# WIRELESS.net
KiCad netlist of a schematic drawn in Altium Designer
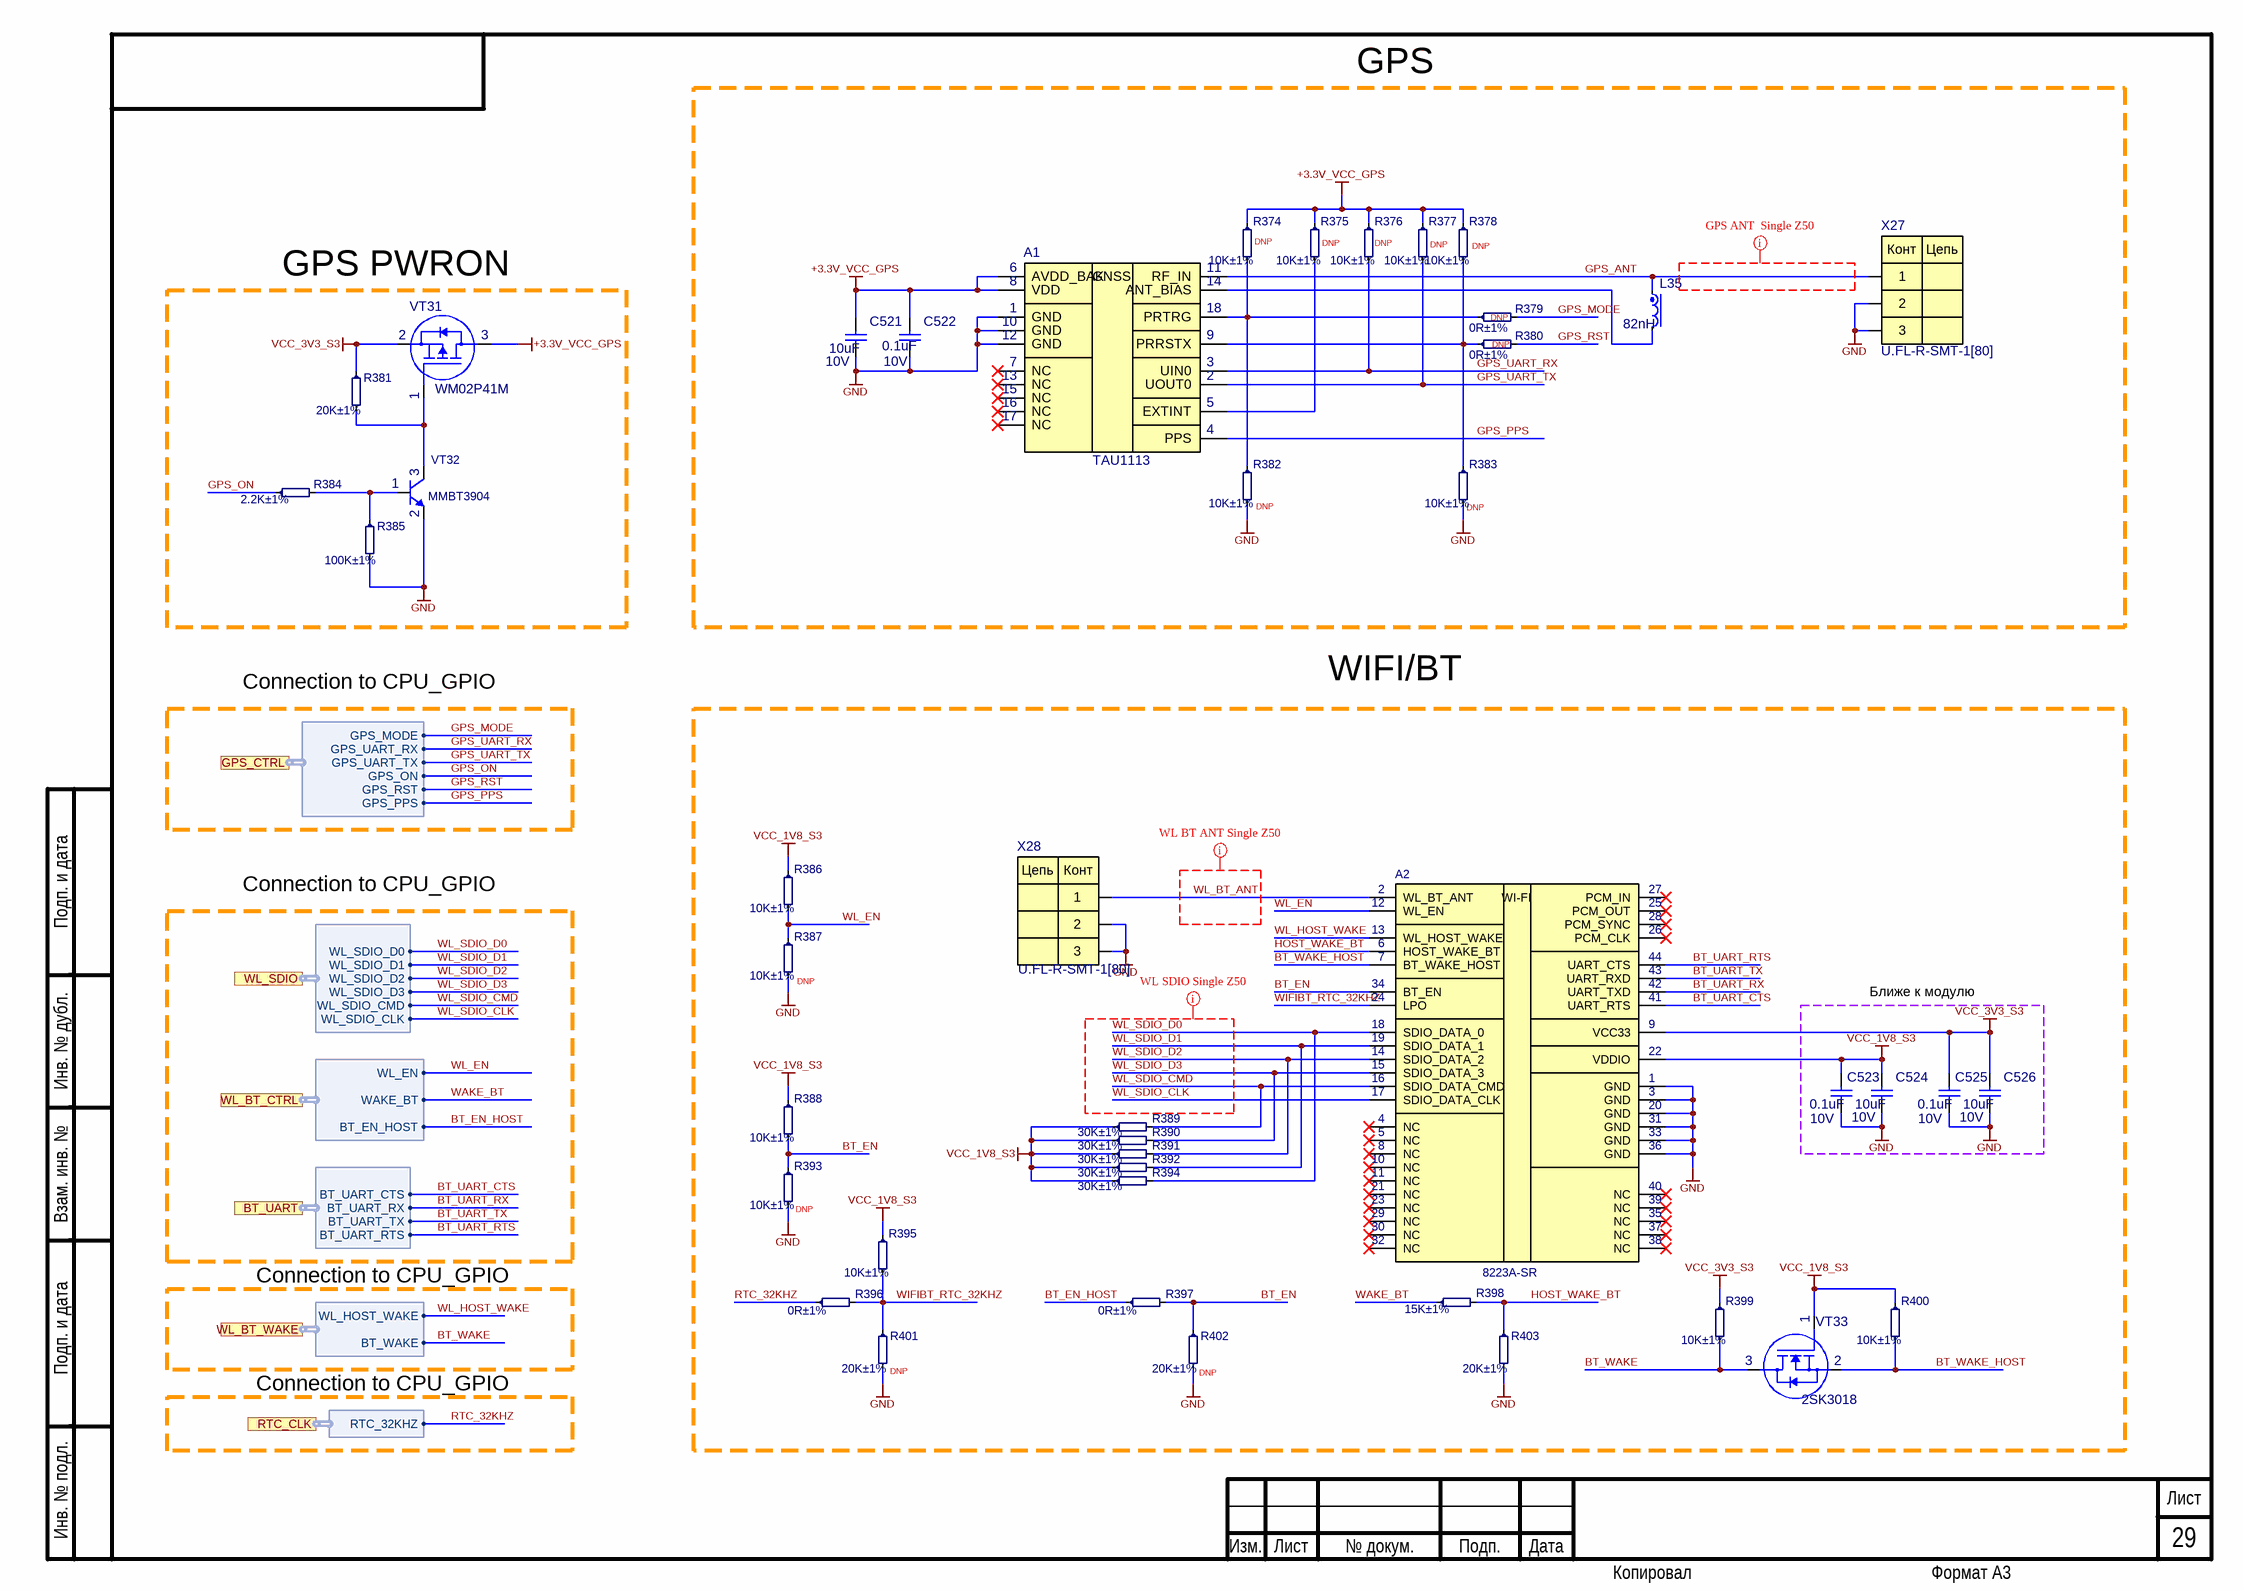
[diagram p0: WIRELESS.SchDoc]

(export (version "E")
  (design (tool "Eeschema 10.0.6"))
  (components
    (comp (ref "A1")
      (value "TAU1113")
      (footprint "TAU1103")
      (description "GNSS Positioning Module")
      (fields (field (name "MANUFACTURER") "Allystar"))
      (libsource (lib "ATB") (part "TAU1103"))
    )
    (comp (ref "A2")
      (value "8223A-SR")
      (footprint "FG6233ASRB-01")
      (description "WIFI/BT")
      (fields (field (name "MANUFACTURER") "FN-LINK"))
      (libsource (lib "LIB_RK") (part "FG6233ASRB-01"))
    )
    (comp (ref "C521")
      (value "10uF")
      (footprint "C0402")
      (fields
        (field (name "PART NUMBER") "0402-X5R-10V-10uF±20")
        (field (name "VOLTAGE") "10V")
        (field (name "TOLERANCE") "20%")
        (field (name "MANUFACTURER") "Samsung")
      )
      (libsource (lib "ATB") (part "C"))
    )
    (comp (ref "C522")
      (value "0.1uF")
      (footprint "C0402")
      (fields
        (field (name "PART NUMBER") "0402-X5R-10V-0.1uF±10%")
        (field (name "VOLTAGE") "10V")
        (field (name "TOLERANCE") "10%")
        (field (name "MANUFACTURER") "Yageo")
      )
      (libsource (lib "ATB") (part "C"))
    )
    (comp (ref "C523")
      (value "0.1uF")
      (footprint "C0402")
      (fields
        (field (name "PART NUMBER") "0402-X5R-10V-0.1uF±10%")
        (field (name "VOLTAGE") "10V")
        (field (name "TOLERANCE") "10%")
        (field (name "MANUFACTURER") "Yageo")
      )
      (libsource (lib "ATB") (part "C"))
    )
    (comp (ref "C524")
      (value "10uF")
      (footprint "C0402")
      (fields
        (field (name "PART NUMBER") "0402-X5R-10V-10uF±20%")
        (field (name "VOLTAGE") "10V")
        (field (name "TOLERANCE") "20%")
        (field (name "MANUFACTURER") "Murata Electronics")
      )
      (libsource (lib "ATB") (part "C"))
    )
    (comp (ref "C525")
      (value "0.1uF")
      (footprint "C0402")
      (fields
        (field (name "PART NUMBER") "0402-X5R-10V-0.1uF±10%")
        (field (name "VOLTAGE") "10V")
        (field (name "TOLERANCE") "10%")
        (field (name "MANUFACTURER") "Yageo")
      )
      (libsource (lib "ATB") (part "C"))
    )
    (comp (ref "C526")
      (value "10uF")
      (footprint "C0402")
      (fields
        (field (name "PART NUMBER") "0402-X5R-10V-10uF±20%")
        (field (name "VOLTAGE") "10V")
        (field (name "TOLERANCE") "20%")
        (field (name "MANUFACTURER") "Murata Electronics")
      )
      (libsource (lib "ATB") (part "C"))
    )
    (comp (ref "L35")
      (value "82nH")
      (footprint "L0402")
      (fields
        (field (name "PART NUMBER") "0402-150mA-82nH±5%")
        (field (name "TOLERANCE") "5%")
        (field (name "MANUFACTURER") "Murata Electronics")
      )
      (libsource (lib "ATB") (part "L"))
    )
    (comp (ref "R374")
      (value "10K±1%")
      (footprint "R0402")
      (description "Chip Resistor 0402 10kΩ ±1% 50V ±100ppm/℃ Thick Film")
      (fields (field (name "PART NUMBER") "0402-0.0625W-10K-100ppm±1%") (field (name "TOLERANCE") "1%"))
      (libsource (lib "ATB") (part "R"))
    )
    (comp (ref "R375")
      (value "10K±1%")
      (footprint "R0402")
      (description "Chip Resistor 0402 10kΩ ±1% 50V ±100ppm/℃ Thick Film")
      (fields (field (name "PART NUMBER") "0402-0.0625W-10K-100ppm±1%") (field (name "TOLERANCE") "1%"))
      (libsource (lib "ATB") (part "R"))
    )
    (comp (ref "R376")
      (value "10K±1%")
      (footprint "R0402")
      (description "Chip Resistor 0402 10kΩ ±1% 50V ±100ppm/℃ Thick Film")
      (fields (field (name "PART NUMBER") "0402-0.0625W-10K-100ppm±1%") (field (name "TOLERANCE") "1%"))
      (libsource (lib "ATB") (part "R"))
    )
    (comp (ref "R377")
      (value "10K±1%")
      (footprint "R0402")
      (description "Chip Resistor 0402 10kΩ ±1% 50V ±100ppm/℃ Thick Film")
      (fields (field (name "PART NUMBER") "0402-0.0625W-10K-100ppm±1%") (field (name "TOLERANCE") "1%"))
      (libsource (lib "ATB") (part "R"))
    )
    (comp (ref "R378")
      (value "10K±1%")
      (footprint "R0402")
      (description "Chip Resistor 0402 10kΩ ±1% 50V ±100ppm/℃ Thick Film")
      (fields (field (name "PART NUMBER") "0402-0.0625W-10K-100ppm±1%") (field (name "TOLERANCE") "1%"))
      (libsource (lib "ATB") (part "R"))
    )
    (comp (ref "R379")
      (value "0R±1%")
      (footprint "R0402")
      (description "Chip Resistor 0402 0Ω ±1% 50V ±100ppm/℃ Thick Film")
      (fields (field (name "PART NUMBER") "0402-0.0625W-0R-100ppm±1%") (field (name "TOLERANCE") "1%"))
      (libsource (lib "ATB") (part "R"))
    )
    (comp (ref "R380")
      (value "0R±1%")
      (footprint "R0402")
      (description "Chip Resistor 0402 0Ω ±1% 50V ±100ppm/℃ Thick Film")
      (fields (field (name "PART NUMBER") "0402-0.0625W-0R-100ppm±1%") (field (name "TOLERANCE") "1%"))
      (libsource (lib "ATB") (part "R"))
    )
    (comp (ref "R381")
      (value "20K±1%")
      (footprint "R0402")
      (description "Chip Resistor 0402 20kΩ ±1% 50V ±100ppm/℃ Thick Film")
      (fields (field (name "PART NUMBER") "0402-0.0625W-20K-100ppm±1%") (field (name "TOLERANCE") "1%"))
      (libsource (lib "ATB") (part "R"))
    )
    (comp (ref "R382")
      (value "10K±1%")
      (footprint "R0402")
      (description "Chip Resistor 0402 10kΩ ±1% 50V ±100ppm/℃ Thick Film")
      (fields (field (name "PART NUMBER") "0402-0.0625W-10K-100ppm±1%") (field (name "TOLERANCE") "1%"))
      (libsource (lib "ATB") (part "R"))
    )
    (comp (ref "R383")
      (value "10K±1%")
      (footprint "R0402")
      (description "Chip Resistor 0402 10kΩ ±1% 50V ±100ppm/℃ Thick Film")
      (fields (field (name "PART NUMBER") "0402-0.0625W-10K-100ppm±1%") (field (name "TOLERANCE") "1%"))
      (libsource (lib "ATB") (part "R"))
    )
    (comp (ref "R384")
      (value "2.2K±1%")
      (footprint "R0402")
      (fields
        (field (name "PART NUMBER") "0402-0.0625W-2.2K-100ppm±1%")
        (field (name "TOLERANCE") "1%")
        (field (name "MANUFACTURER") "Yageo")
      )
      (libsource (lib "ATB") (part "R"))
    )
    (comp (ref "R385")
      (value "100K±1%")
      (footprint "R0402")
      (description "Chip Resistor 0402 100kΩ ±1% 50V ±100ppm/℃ Thick Film")
      (fields (field (name "PART NUMBER") "0402-0.0625W-100K-100ppm±1%") (field (name "TOLERANCE") "1%"))
      (libsource (lib "ATB") (part "R"))
    )
    (comp (ref "R386")
      (value "10K±1%")
      (footprint "R0402")
      (description "Chip Resistor 0402 10kΩ ±1% 50V ±100ppm/℃ Thick Film")
      (fields (field (name "PART NUMBER") "0402-0.0625W-10K-100ppm±1%") (field (name "TOLERANCE") "1%"))
      (libsource (lib "ATB") (part "R"))
    )
    (comp (ref "R387")
      (value "10K±1%")
      (footprint "R0402")
      (description "Chip Resistor 0402 10kΩ ±1% 50V ±100ppm/℃ Thick Film")
      (fields (field (name "PART NUMBER") "0402-0.0625W-10K-100ppm±1%") (field (name "TOLERANCE") "1%"))
      (libsource (lib "ATB") (part "R"))
    )
    (comp (ref "R388")
      (value "10K±1%")
      (footprint "R0402")
      (description "Chip Resistor 0402 10kΩ ±1% 50V ±100ppm/℃ Thick Film")
      (fields (field (name "PART NUMBER") "0402-0.0625W-10K-100ppm±1%") (field (name "TOLERANCE") "1%"))
      (libsource (lib "ATB") (part "R"))
    )
    (comp (ref "R389")
      (value "30K±1%")
      (footprint "R0402")
      (fields
        (field (name "PART NUMBER") "0402-0.0625W-30K-100ppm±1%")
        (field (name "TOLERANCE") "1%")
        (field (name "MANUFACTURER") "Yageo")
      )
      (libsource (lib "ATB") (part "R"))
    )
    (comp (ref "R390")
      (value "30K±1%")
      (footprint "R0402")
      (fields
        (field (name "PART NUMBER") "0402-0.0625W-30K-100ppm±1%")
        (field (name "TOLERANCE") "1%")
        (field (name "MANUFACTURER") "Yageo")
      )
      (libsource (lib "ATB") (part "R"))
    )
    (comp (ref "R391")
      (value "30K±1%")
      (footprint "R0402")
      (fields
        (field (name "PART NUMBER") "0402-0.0625W-30K-100ppm±1%")
        (field (name "TOLERANCE") "1%")
        (field (name "MANUFACTURER") "Yageo")
      )
      (libsource (lib "ATB") (part "R"))
    )
    (comp (ref "R392")
      (value "30K±1%")
      (footprint "R0402")
      (fields
        (field (name "PART NUMBER") "0402-0.0625W-30K-100ppm±1%")
        (field (name "TOLERANCE") "1%")
        (field (name "MANUFACTURER") "Yageo")
      )
      (libsource (lib "ATB") (part "R"))
    )
    (comp (ref "R393")
      (value "10K±1%")
      (footprint "R0402")
      (description "Chip Resistor 0402 10kΩ ±1% 50V ±100ppm/℃ Thick Film")
      (fields (field (name "PART NUMBER") "0402-0.0625W-10K-100ppm±1%") (field (name "TOLERANCE") "1%"))
      (libsource (lib "ATB") (part "R"))
    )
    (comp (ref "R394")
      (value "30K±1%")
      (footprint "R0402")
      (fields
        (field (name "PART NUMBER") "0402-0.0625W-30K-100ppm±1%")
        (field (name "TOLERANCE") "1%")
        (field (name "MANUFACTURER") "Yageo")
      )
      (libsource (lib "ATB") (part "R"))
    )
    (comp (ref "R395")
      (value "10K±1%")
      (footprint "R0402")
      (description "Chip Resistor 0402 10kΩ ±1% 50V ±100ppm/℃ Thick Film")
      (fields (field (name "PART NUMBER") "0402-0.0625W-10K-100ppm±1%") (field (name "TOLERANCE") "1%"))
      (libsource (lib "ATB") (part "R"))
    )
    (comp (ref "R396")
      (value "0R±1%")
      (footprint "R0402")
      (description "Chip Resistor 0402 0Ω ±1% 50V ±100ppm/℃ Thick Film")
      (fields (field (name "PART NUMBER") "0402-0.0625W-0R-100ppm±1%") (field (name "TOLERANCE") "1%"))
      (libsource (lib "ATB") (part "R"))
    )
    (comp (ref "R397")
      (value "0R±1%")
      (footprint "R0402")
      (description "Chip Resistor 0402 0Ω ±1% 50V ±100ppm/℃ Thick Film")
      (fields (field (name "PART NUMBER") "0402-0.0625W-0R-100ppm±1%") (field (name "TOLERANCE") "1%"))
      (libsource (lib "ATB") (part "R"))
    )
    (comp (ref "R398")
      (value "15K±1%")
      (footprint "R0402")
      (fields
        (field (name "PART NUMBER") "0402-0.0625W-15K-100ppm±1%")
        (field (name "TOLERANCE") "1%")
        (field (name "MANUFACTURER") "Viking Tech Corp.(VIKING)")
      )
      (libsource (lib "ATB") (part "R"))
    )
    (comp (ref "R399")
      (value "10K±1%")
      (footprint "R0402")
      (description "Chip Resistor 0402 10kΩ ±1% 50V ±100ppm/℃ Thick Film")
      (fields (field (name "PART NUMBER") "0402-0.0625W-10K-100ppm±1%") (field (name "TOLERANCE") "1%"))
      (libsource (lib "ATB") (part "R"))
    )
    (comp (ref "R400")
      (value "10K±1%")
      (footprint "R0402")
      (description "Chip Resistor 0402 10kΩ ±1% 50V ±100ppm/℃ Thick Film")
      (fields (field (name "PART NUMBER") "0402-0.0625W-10K-100ppm±1%") (field (name "TOLERANCE") "1%"))
      (libsource (lib "ATB") (part "R"))
    )
    (comp (ref "R401")
      (value "20K±1%")
      (footprint "R0402")
      (description "Chip Resistor 0402 20kΩ ±1% 50V ±100ppm/℃ Thick Film")
      (fields (field (name "PART NUMBER") "0402-0.0625W-20K-100ppm±1%") (field (name "TOLERANCE") "1%"))
      (libsource (lib "ATB") (part "R"))
    )
    (comp (ref "R402")
      (value "20K±1%")
      (footprint "R0402")
      (description "Chip Resistor 0402 20kΩ ±1% 50V ±100ppm/℃ Thick Film")
      (fields (field (name "PART NUMBER") "0402-0.0625W-20K-100ppm±1%") (field (name "TOLERANCE") "1%"))
      (libsource (lib "ATB") (part "R"))
    )
    (comp (ref "R403")
      (value "20K±1%")
      (footprint "R0402")
      (description "Chip Resistor 0402 20kΩ ±1% 50V ±100ppm/℃ Thick Film")
      (fields (field (name "PART NUMBER") "0402-0.0625W-20K-100ppm±1%") (field (name "TOLERANCE") "1%"))
      (libsource (lib "ATB") (part "R"))
    )
    (comp (ref "VT31")
      (value "WM02P41M")
      (footprint "SOT23")
      (description "Small signal mosfet")
      (fields (field (name "VOLTAGE") "-20V") (field (name "MANUFACTURER") "Wayon"))
      (libsource (lib "ATB") (part "WM02P41M"))
    )
    (comp (ref "VT32")
      (value "MMBT3904")
      (footprint "SOT23")
      (description "NPN transistor")
      (fields (field (name "VOLTAGE") "40V") (field (name "MANUFACTURER") "Diotec Semiconductor"))
      (libsource (lib "ATB") (part "BC846BLT1G"))
    )
    (comp (ref "VT33")
      (value "2SK3018")
      (footprint "2SK3018")
      (description "N-Channel")
      (fields (field (name "MANUFACTURER") "KUU"))
      (libsource (lib "LIB_RK") (part "2SK3018"))
    )
    (comp (ref "X27")
      (value "U.FL-R-SMT-1[80]")
      (footprint "1909763-1")
      (description "U.FL-R-SMT-1")
      (fields (field (name "MANUFACTURER") "TE Connectivity"))
      (libsource (lib "ATB") (part "H3"))
    )
    (comp (ref "X28")
      (value "U.FL-R-SMT-1[80]")
      (footprint "1909763-1")
      (description "U.FL-R-SMT-1")
      (fields (field (name "MANUFACTURER") "TE Connectivity"))
      (libsource (lib "") (part "H3_1"))
    )
  )
  (nets
    (net (code "7") (name "+3.3V_VCC_GPS") (class "Default")
      (node (ref "A1") (pin "6") (pinfunction "AVDD_BAK_6") (pintype "passive"))
      (node (ref "A1") (pin "8") (pinfunction "VDD_8") (pintype "passive"))
      (node (ref "C521") (pin "2") (pinfunction "2_2") (pintype "passive"))
      (node (ref "C522") (pin "2") (pinfunction "2_2") (pintype "passive"))
      (node (ref "R374") (pin "1") (pinfunction "1_1") (pintype "passive"))
      (node (ref "R375") (pin "1") (pinfunction "1_1") (pintype "passive"))
      (node (ref "R376") (pin "1") (pinfunction "1_1") (pintype "passive"))
      (node (ref "R377") (pin "1") (pinfunction "1_1") (pintype "passive"))
      (node (ref "R378") (pin "1") (pinfunction "1_1") (pintype "passive"))
      (node (ref "VT31") (pin "3") (pinfunction "3_3") (pintype "passive"))
    )
    (net (code "8") (name "/BT_EN") (class "Default")
      (node (ref "A2") (pin "34") (pinfunction "BT_EN_34") (pintype "passive"))
      (node (ref "R388") (pin "2") (pinfunction "2_2") (pintype "passive"))
      (node (ref "R393") (pin "1") (pinfunction "1_1") (pintype "passive"))
      (node (ref "R397") (pin "2") (pinfunction "2_2") (pintype "passive"))
      (node (ref "R402") (pin "1") (pinfunction "1_1") (pintype "passive"))
    )
    (net (code "9") (name "/BT_EN_HOST") (class "Default")
      (node (ref "R397") (pin "1") (pinfunction "1_1") (pintype "passive"))
    )
    (net (code "10") (name "/BT_UART_CTS") (class "Default")
      (node (ref "A2") (pin "41") (pinfunction "UART_RTS_41") (pintype "passive"))
    )
    (net (code "11") (name "/BT_UART_RTS") (class "Default")
      (node (ref "A2") (pin "44") (pinfunction "UART_CTS_44") (pintype "passive"))
    )
    (net (code "12") (name "/BT_UART_RX") (class "Default")
      (node (ref "A2") (pin "42") (pinfunction "UART_TXD_42") (pintype "passive"))
    )
    (net (code "13") (name "/BT_UART_TX") (class "Default")
      (node (ref "A2") (pin "43") (pinfunction "UART_RXD_43") (pintype "passive"))
    )
    (net (code "14") (name "/BT_WAKE") (class "Default")
      (node (ref "R399") (pin "2") (pinfunction "2_2") (pintype "passive"))
      (node (ref "VT33") (pin "3") (pinfunction "D_3") (pintype "passive"))
    )
    (net (code "15") (name "/BT_WAKE_HOST") (class "Default")
      (node (ref "A2") (pin "7") (pinfunction "BT_WAKE_HOST_7") (pintype "passive"))
      (node (ref "R400") (pin "2") (pinfunction "2_2") (pintype "passive"))
      (node (ref "VT33") (pin "2") (pinfunction "S_2") (pintype "passive"))
    )
    (net (code "16") (name "/GPS_ANT") (class "Default")
      (node (ref "A1") (pin "11") (pinfunction "RF_IN_11") (pintype "passive"))
      (node (ref "L35") (pin "1") (pinfunction "1_1") (pintype "passive"))
      (node (ref "X27") (pin "1") (pinfunction "1_1") (pintype "passive"))
    )
    (net (code "17") (name "/GPS_MODE") (class "Default")
      (node (ref "R379") (pin "2") (pinfunction "2_2") (pintype "passive"))
    )
    (net (code "18") (name "/GPS_ON") (class "Default")
      (node (ref "R384") (pin "1") (pinfunction "1_1") (pintype "passive"))
    )
    (net (code "19") (name "/GPS_PPS") (class "Default")
      (node (ref "A1") (pin "4") (pinfunction "PPS_4") (pintype "passive"))
    )
    (net (code "20") (name "/GPS_RST") (class "Default")
      (node (ref "R380") (pin "2") (pinfunction "2_2") (pintype "passive"))
    )
    (net (code "21") (name "/GPS_UART_RX") (class "Default")
      (node (ref "A1") (pin "3") (pinfunction "UIN0_3") (pintype "passive"))
      (node (ref "R376") (pin "2") (pinfunction "2_2") (pintype "passive"))
    )
    (net (code "22") (name "/GPS_UART_TX") (class "Default")
      (node (ref "A1") (pin "2") (pinfunction "UOUT0_2") (pintype "passive"))
      (node (ref "R377") (pin "2") (pinfunction "2_2") (pintype "passive"))
    )
    (net (code "23") (name "/HOST_WAKE_BT") (class "Default")
      (node (ref "A2") (pin "6") (pinfunction "HOST_WAKE_BT_6") (pintype "passive"))
      (node (ref "R398") (pin "2") (pinfunction "2_2") (pintype "passive"))
      (node (ref "R403") (pin "1") (pinfunction "1_1") (pintype "passive"))
    )
    (net (code "24") (name "/RTC_32KHZ") (class "Default")
      (node (ref "R396") (pin "1") (pinfunction "1_1") (pintype "passive"))
    )
    (net (code "25") (name "/WAKE_BT") (class "Default")
      (node (ref "R398") (pin "1") (pinfunction "1_1") (pintype "passive"))
    )
    (net (code "26") (name "/WIFIBT_RTC_32KHZ") (class "Default")
      (node (ref "A2") (pin "24") (pinfunction "LPO_24") (pintype "passive"))
      (node (ref "R395") (pin "2") (pinfunction "2_2") (pintype "passive"))
      (node (ref "R396") (pin "2") (pinfunction "2_2") (pintype "passive"))
      (node (ref "R401") (pin "1") (pinfunction "1_1") (pintype "passive"))
    )
    (net (code "27") (name "/WL_BT_ANT") (class "Default")
      (node (ref "A2") (pin "2") (pinfunction "WL_BT_ANT_2") (pintype "passive"))
      (node (ref "X28") (pin "1") (pinfunction "1_1") (pintype "passive"))
    )
    (net (code "28") (name "/WL_EN") (class "Default")
      (node (ref "A2") (pin "12") (pinfunction "WL_EN_12") (pintype "passive"))
      (node (ref "R386") (pin "2") (pinfunction "2_2") (pintype "passive"))
      (node (ref "R387") (pin "1") (pinfunction "1_1") (pintype "passive"))
    )
    (net (code "29") (name "/WL_HOST_WAKE") (class "Default")
      (node (ref "A2") (pin "13") (pinfunction "WL_HOST_WAKE_13") (pintype "passive"))
    )
    (net (code "30") (name "/WL_SDIO_CLK") (class "Default")
      (node (ref "A2") (pin "17") (pinfunction "SDIO_DATA_CLK_17") (pintype "passive"))
    )
    (net (code "31") (name "/WL_SDIO_CMD") (class "Default")
      (node (ref "A2") (pin "16") (pinfunction "SDIO_DATA_CMD_16") (pintype "passive"))
      (node (ref "R389") (pin "2") (pinfunction "2_2") (pintype "passive"))
    )
    (net (code "32") (name "/WL_SDIO_D0") (class "Default")
      (node (ref "A2") (pin "18") (pinfunction "SDIO_DATA_0_18") (pintype "passive"))
      (node (ref "R394") (pin "2") (pinfunction "2_2") (pintype "passive"))
    )
    (net (code "33") (name "/WL_SDIO_D1") (class "Default")
      (node (ref "A2") (pin "19") (pinfunction "SDIO_DATA_1_19") (pintype "passive"))
      (node (ref "R392") (pin "2") (pinfunction "2_2") (pintype "passive"))
    )
    (net (code "34") (name "/WL_SDIO_D2") (class "Default")
      (node (ref "A2") (pin "14") (pinfunction "SDIO_DATA_2_14") (pintype "passive"))
      (node (ref "R391") (pin "2") (pinfunction "2_2") (pintype "passive"))
    )
    (net (code "35") (name "/WL_SDIO_D3") (class "Default")
      (node (ref "A2") (pin "15") (pinfunction "SDIO_DATA_3_15") (pintype "passive"))
      (node (ref "R390") (pin "2") (pinfunction "2_2") (pintype "passive"))
    )
    (net (code "42") (name "GND") (class "Default")
      (node (ref "A1") (pin "1") (pinfunction "GND_1") (pintype "passive"))
      (node (ref "A1") (pin "10") (pinfunction "GND_10") (pintype "passive"))
      (node (ref "A1") (pin "12") (pinfunction "GND_12") (pintype "passive"))
      (node (ref "A2") (pin "1") (pinfunction "GND_1") (pintype "passive"))
      (node (ref "A2") (pin "20") (pinfunction "GND_20") (pintype "passive"))
      (node (ref "A2") (pin "3") (pinfunction "GND_3") (pintype "passive"))
      (node (ref "A2") (pin "31") (pinfunction "GND_31") (pintype "passive"))
      (node (ref "A2") (pin "33") (pinfunction "GND_33") (pintype "passive"))
      (node (ref "A2") (pin "36") (pinfunction "GND_36") (pintype "passive"))
      (node (ref "C521") (pin "1") (pinfunction "1_1") (pintype "passive"))
      (node (ref "C522") (pin "1") (pinfunction "1_1") (pintype "passive"))
      (node (ref "C523") (pin "1") (pinfunction "1_1") (pintype "passive"))
      (node (ref "C524") (pin "1") (pinfunction "1_1") (pintype "passive"))
      (node (ref "C525") (pin "1") (pinfunction "1_1") (pintype "passive"))
      (node (ref "C526") (pin "1") (pinfunction "1_1") (pintype "passive"))
      (node (ref "R382") (pin "2") (pinfunction "2_2") (pintype "passive"))
      (node (ref "R383") (pin "2") (pinfunction "2_2") (pintype "passive"))
      (node (ref "R385") (pin "2") (pinfunction "2_2") (pintype "passive"))
      (node (ref "R387") (pin "2") (pinfunction "2_2") (pintype "passive"))
      (node (ref "R393") (pin "2") (pinfunction "2_2") (pintype "passive"))
      (node (ref "R401") (pin "2") (pinfunction "2_2") (pintype "passive"))
      (node (ref "R402") (pin "2") (pinfunction "2_2") (pintype "passive"))
      (node (ref "R403") (pin "2") (pinfunction "2_2") (pintype "passive"))
      (node (ref "VT32") (pin "2") (pinfunction "E_2") (pintype "passive"))
      (node (ref "X27") (pin "2") (pinfunction "2_2") (pintype "passive"))
      (node (ref "X27") (pin "3") (pinfunction "3_3") (pintype "passive"))
      (node (ref "X28") (pin "2") (pinfunction "2_2") (pintype "passive"))
      (node (ref "X28") (pin "3") (pinfunction "3_3") (pintype "passive"))
    )
    (net (code "43") (name "Net-(A1-ANT_BIAS)") (class "Default")
      (node (ref "A1") (pin "14") (pinfunction "ANT_BIAS_14") (pintype "passive"))
      (node (ref "L35") (pin "2") (pinfunction "2_2") (pintype "passive"))
    )
    (net (code "44") (name "Net-(A1-EXTINT)") (class "Default")
      (node (ref "A1") (pin "5") (pinfunction "EXTINT_5") (pintype "passive"))
      (node (ref "R375") (pin "2") (pinfunction "2_2") (pintype "passive"))
    )
    (net (code "45") (name "Net-(A1-PRRSTX)") (class "Default")
      (node (ref "A1") (pin "9") (pinfunction "PRRSTX_9") (pintype "passive"))
      (node (ref "R378") (pin "2") (pinfunction "2_2") (pintype "passive"))
      (node (ref "R380") (pin "1") (pinfunction "1_1") (pintype "passive"))
      (node (ref "R383") (pin "1") (pinfunction "1_1") (pintype "passive"))
    )
    (net (code "46") (name "Net-(A1-PRTRG)") (class "Default")
      (node (ref "A1") (pin "18") (pinfunction "PRTRG_18") (pintype "passive"))
      (node (ref "R374") (pin "2") (pinfunction "2_2") (pintype "passive"))
      (node (ref "R379") (pin "1") (pinfunction "1_1") (pintype "passive"))
      (node (ref "R382") (pin "1") (pinfunction "1_1") (pintype "passive"))
    )
    (net (code "47") (name "Net-(VT32-B)") (class "Default")
      (node (ref "R384") (pin "2") (pinfunction "2_2") (pintype "passive"))
      (node (ref "R385") (pin "1") (pinfunction "1_1") (pintype "passive"))
      (node (ref "VT32") (pin "1") (pinfunction "B_1") (pintype "passive"))
    )
    (net (code "48") (name "Net-(VT32-C)") (class "Default")
      (node (ref "R381") (pin "2") (pinfunction "2_2") (pintype "passive"))
      (node (ref "VT31") (pin "1") (pinfunction "1_1") (pintype "passive"))
      (node (ref "VT32") (pin "3") (pinfunction "C_3") (pintype "passive"))
    )
    (net (code "49") (name "VCC_1V8_S3") (class "Default")
      (node (ref "A2") (pin "22") (pinfunction "VDDIO_22") (pintype "passive"))
      (node (ref "C523") (pin "2") (pinfunction "2_2") (pintype "passive"))
      (node (ref "C524") (pin "2") (pinfunction "2_2") (pintype "passive"))
      (node (ref "R386") (pin "1") (pinfunction "1_1") (pintype "passive"))
      (node (ref "R388") (pin "1") (pinfunction "1_1") (pintype "passive"))
      (node (ref "R389") (pin "1") (pinfunction "1_1") (pintype "passive"))
      (node (ref "R390") (pin "1") (pinfunction "1_1") (pintype "passive"))
      (node (ref "R391") (pin "1") (pinfunction "1_1") (pintype "passive"))
      (node (ref "R392") (pin "1") (pinfunction "1_1") (pintype "passive"))
      (node (ref "R394") (pin "1") (pinfunction "1_1") (pintype "passive"))
      (node (ref "R395") (pin "1") (pinfunction "1_1") (pintype "passive"))
      (node (ref "R400") (pin "1") (pinfunction "1_1") (pintype "passive"))
      (node (ref "VT33") (pin "1") (pinfunction "G_1") (pintype "passive"))
    )
    (net (code "50") (name "VCC_3V3_S3") (class "Default")
      (node (ref "A2") (pin "9") (pinfunction "VCC33_9") (pintype "passive"))
      (node (ref "C525") (pin "2") (pinfunction "2_2") (pintype "passive"))
      (node (ref "C526") (pin "2") (pinfunction "2_2") (pintype "passive"))
      (node (ref "R381") (pin "1") (pinfunction "1_1") (pintype "passive"))
      (node (ref "R399") (pin "1") (pinfunction "1_1") (pintype "passive"))
      (node (ref "VT31") (pin "2") (pinfunction "2_2") (pintype "passive"))
    )
    (net (code "51") (name "unconnected-(A1-NC-Pad7)") (class "Default")
      (node (ref "A1") (pin "7") (pinfunction "NC_7") (pintype "passive+no_connect"))
    )
    (net (code "52") (name "unconnected-(A1-NC-Pad13)") (class "Default")
      (node (ref "A1") (pin "13") (pinfunction "NC_13") (pintype "passive+no_connect"))
    )
    (net (code "53") (name "unconnected-(A1-NC-Pad15)") (class "Default")
      (node (ref "A1") (pin "15") (pinfunction "NC_15") (pintype "passive+no_connect"))
    )
    (net (code "54") (name "unconnected-(A1-NC-Pad16)") (class "Default")
      (node (ref "A1") (pin "16") (pinfunction "NC_16") (pintype "passive+no_connect"))
    )
    (net (code "55") (name "unconnected-(A1-NC-Pad17)") (class "Default")
      (node (ref "A1") (pin "17") (pinfunction "NC_17") (pintype "passive+no_connect"))
    )
    (net (code "56") (name "unconnected-(A2-NC-Pad4)") (class "Default")
      (node (ref "A2") (pin "4") (pinfunction "NC_4") (pintype "passive+no_connect"))
    )
    (net (code "57") (name "unconnected-(A2-NC-Pad5)") (class "Default")
      (node (ref "A2") (pin "5") (pinfunction "NC_5") (pintype "passive+no_connect"))
    )
    (net (code "58") (name "unconnected-(A2-NC-Pad8)") (class "Default")
      (node (ref "A2") (pin "8") (pinfunction "NC_8") (pintype "passive+no_connect"))
    )
    (net (code "59") (name "unconnected-(A2-NC-Pad10)") (class "Default")
      (node (ref "A2") (pin "10") (pinfunction "NC_10") (pintype "passive+no_connect"))
    )
    (net (code "60") (name "unconnected-(A2-NC-Pad11)") (class "Default")
      (node (ref "A2") (pin "11") (pinfunction "NC_11") (pintype "passive+no_connect"))
    )
    (net (code "61") (name "unconnected-(A2-NC-Pad21)") (class "Default")
      (node (ref "A2") (pin "21") (pinfunction "NC_21") (pintype "passive+no_connect"))
    )
    (net (code "62") (name "unconnected-(A2-NC-Pad23)") (class "Default")
      (node (ref "A2") (pin "23") (pinfunction "NC_23") (pintype "passive+no_connect"))
    )
    (net (code "63") (name "unconnected-(A2-NC-Pad29)") (class "Default")
      (node (ref "A2") (pin "29") (pinfunction "NC_29") (pintype "passive+no_connect"))
    )
    (net (code "64") (name "unconnected-(A2-NC-Pad30)") (class "Default")
      (node (ref "A2") (pin "30") (pinfunction "NC_30") (pintype "passive+no_connect"))
    )
    (net (code "65") (name "unconnected-(A2-NC-Pad32)") (class "Default")
      (node (ref "A2") (pin "32") (pinfunction "NC_32") (pintype "passive+no_connect"))
    )
    (net (code "66") (name "unconnected-(A2-NC-Pad35)") (class "Default")
      (node (ref "A2") (pin "35") (pinfunction "NC_35") (pintype "passive+no_connect"))
    )
    (net (code "67") (name "unconnected-(A2-NC-Pad37)") (class "Default")
      (node (ref "A2") (pin "37") (pinfunction "NC_37") (pintype "passive+no_connect"))
    )
    (net (code "68") (name "unconnected-(A2-NC-Pad38)") (class "Default")
      (node (ref "A2") (pin "38") (pinfunction "NC_38") (pintype "passive+no_connect"))
    )
    (net (code "69") (name "unconnected-(A2-NC-Pad39)") (class "Default")
      (node (ref "A2") (pin "39") (pinfunction "NC_39") (pintype "passive+no_connect"))
    )
    (net (code "70") (name "unconnected-(A2-NC-Pad40)") (class "Default")
      (node (ref "A2") (pin "40") (pinfunction "NC_40") (pintype "passive+no_connect"))
    )
    (net (code "71") (name "unconnected-(A2-PCM_CLK-Pad26)") (class "Default")
      (node (ref "A2") (pin "26") (pinfunction "PCM_CLK_26") (pintype "passive+no_connect"))
    )
    (net (code "72") (name "unconnected-(A2-PCM_IN-Pad27)") (class "Default")
      (node (ref "A2") (pin "27") (pinfunction "PCM_IN_27") (pintype "passive+no_connect"))
    )
    (net (code "73") (name "unconnected-(A2-PCM_OUT-Pad25)") (class "Default")
      (node (ref "A2") (pin "25") (pinfunction "PCM_OUT_25") (pintype "passive+no_connect"))
    )
    (net (code "74") (name "unconnected-(A2-PCM_SYNC-Pad28)") (class "Default")
      (node (ref "A2") (pin "28") (pinfunction "PCM_SYNC_28") (pintype "passive+no_connect"))
    )
  )
)
